# base3-5pin-interface.net
KiCad netlist of a schematic drawn in EAGLE
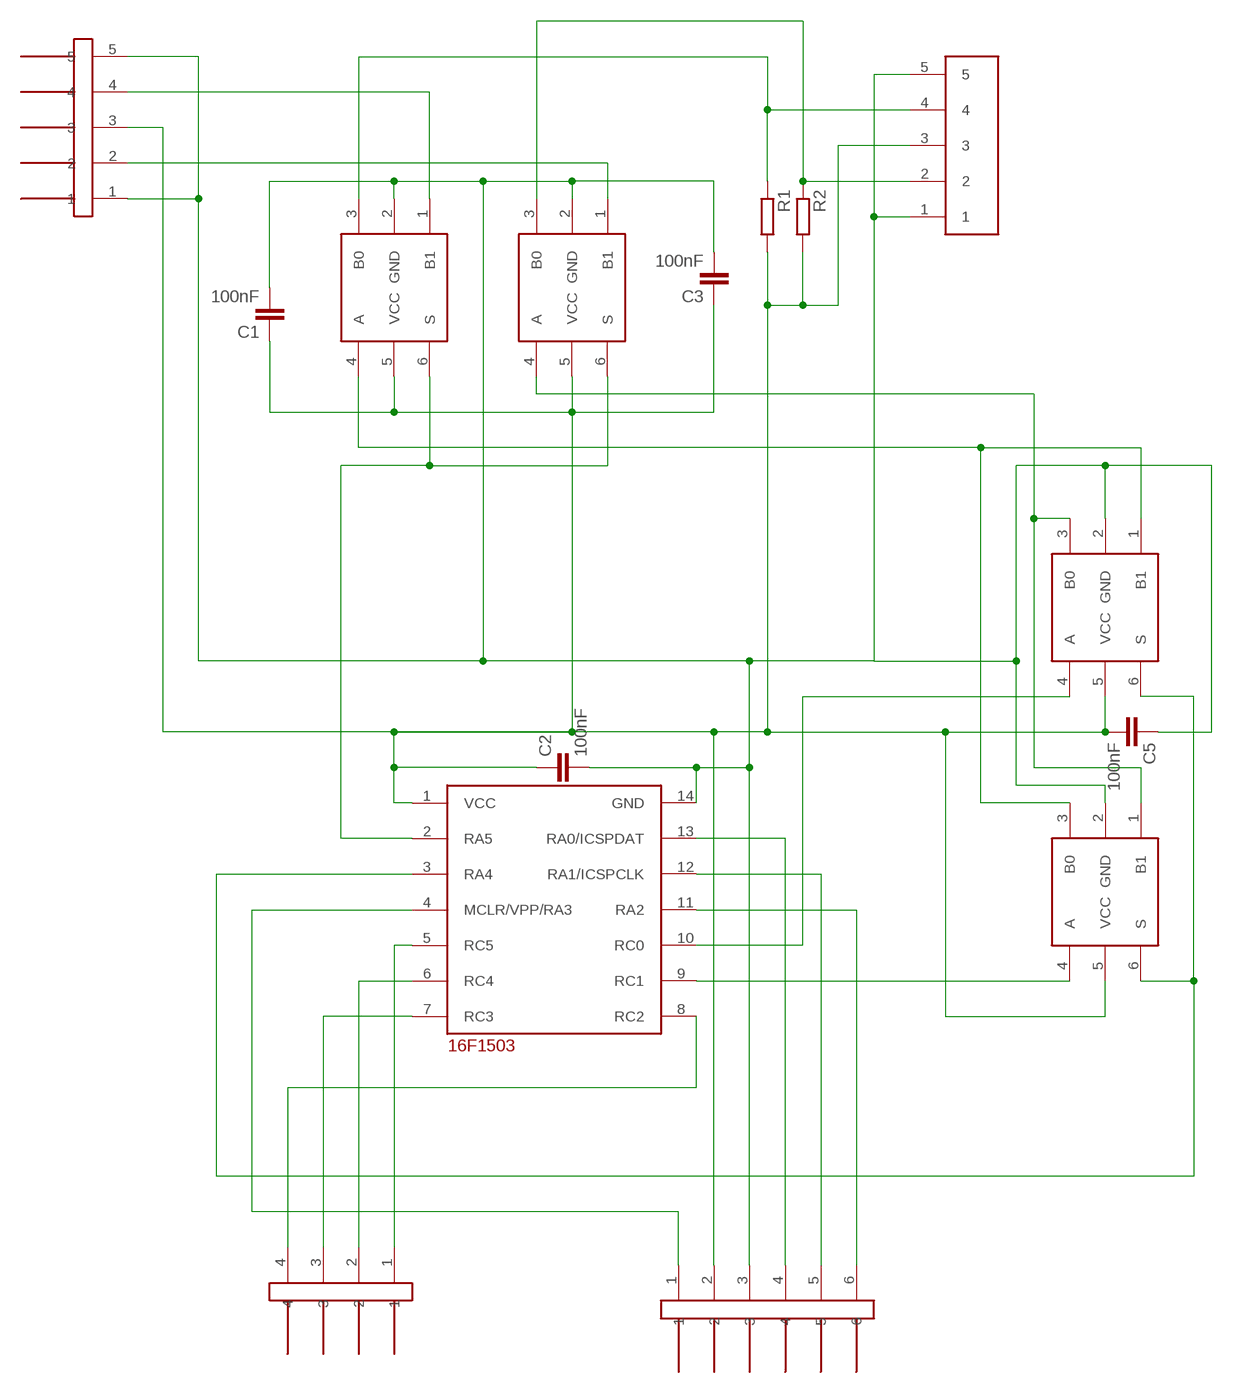
[diagram p0: schematic, sheet 1]

(export (version "E")
  (design (tool "Eeschema 10.0.6"))
  (components
    (comp (ref "C1")
      (value "100nF")
      (footprint "eagle-import:C0805")
      (libsource (lib "eagle-import") (part "C-EUC0805"))
    )
    (comp (ref "C2")
      (value "100nF")
      (footprint "eagle-import:C0805")
      (libsource (lib "eagle-import") (part "C-EUC0805"))
    )
    (comp (ref "C3")
      (value "100nF")
      (footprint "eagle-import:C0805")
      (libsource (lib "eagle-import") (part "C-EUC0805"))
    )
    (comp (ref "C5")
      (value "100nF")
      (footprint "eagle-import:C0805")
      (libsource (lib "eagle-import") (part "C-EUC0805"))
    )
    (comp (ref "IO")
      (value "JUMPER4M")
      (footprint "eagle-import:JUMPER4M")
      (libsource (lib "eagle-import") (part "JUMPER4M"))
    )
    (comp (ref "PROGRAMMER")
      (value "JUMPER6M")
      (footprint "eagle-import:JUMPER6M")
      (libsource (lib "eagle-import") (part "JUMPER6M"))
    )
    (comp (ref "R1")
      (value "R-EU_M0805")
      (footprint "eagle-import:M0805")
      (libsource (lib "eagle-import") (part "R-EU_M0805"))
    )
    (comp (ref "R2")
      (value "R-EU_M0805")
      (footprint "eagle-import:M0805")
      (libsource (lib "eagle-import") (part "R-EU_M0805"))
    )
    (comp (ref "U$1")
      (value "16F103-TSSOP")
      (footprint "eagle-import:TSSOP14")
      (libsource (lib "eagle-import") (part "16F103-TSSOP"))
    )
    (comp (ref "U$2")
      (value "NC7SB3157P6X")
      (footprint "eagle-import:SC70-6L")
      (libsource (lib "eagle-import") (part "NC7SB3157P6X"))
    )
    (comp (ref "U$3")
      (value "NC7SB3157P6X")
      (footprint "eagle-import:SC70-6L")
      (libsource (lib "eagle-import") (part "NC7SB3157P6X"))
    )
    (comp (ref "U$4")
      (value "JUMPER5")
      (footprint "eagle-import:JUMPER5")
      (libsource (lib "eagle-import") (part "JUMPER5"))
    )
    (comp (ref "U$5")
      (value "JUMPER5F")
      (footprint "eagle-import:JUMPER5F")
      (libsource (lib "eagle-import") (part "JUMPER5F"))
    )
    (comp (ref "U$6")
      (value "NC7SB3157P6X")
      (footprint "eagle-import:SC70-6L")
      (libsource (lib "eagle-import") (part "NC7SB3157P6X"))
    )
    (comp (ref "U$7")
      (value "NC7SB3157P6X")
      (footprint "eagle-import:SC70-6L")
      (libsource (lib "eagle-import") (part "NC7SB3157P6X"))
    )
  )
  (nets
    (net (code "1") (name "Net-(U$1-GND)") (class "Default")
      (node (ref "C1") (pin "2") (pinfunction "2_2") (pintype "passive"))
      (node (ref "C2") (pin "2") (pinfunction "2_2") (pintype "passive"))
      (node (ref "C3") (pin "2") (pinfunction "2_2") (pintype "passive"))
      (node (ref "C5") (pin "1") (pinfunction "1_1") (pintype "passive"))
      (node (ref "PROGRAMMER") (pin "3") (pinfunction "3_3") (pintype "bidirectional"))
      (node (ref "U$1") (pin "14") (pinfunction "GND_14") (pintype "power_in"))
      (node (ref "U$2") (pin "2") (pinfunction "GND_2") (pintype "power_in"))
      (node (ref "U$3") (pin "2") (pinfunction "GND_2") (pintype "power_in"))
      (node (ref "U$4") (pin "1") (pinfunction "1_1") (pintype "bidirectional"))
      (node (ref "U$4") (pin "5") (pinfunction "5_5") (pintype "bidirectional"))
      (node (ref "U$5") (pin "1") (pinfunction "1_1") (pintype "bidirectional"))
      (node (ref "U$5") (pin "5") (pinfunction "5_5") (pintype "bidirectional"))
      (node (ref "U$6") (pin "2") (pinfunction "GND_2") (pintype "power_in"))
      (node (ref "U$7") (pin "2") (pinfunction "GND_2") (pintype "power_in"))
    )
    (net (code "2") (name "Net-(U$1-MCLR{slash}VPP{slash}RA3)") (class "Default")
      (node (ref "PROGRAMMER") (pin "1") (pinfunction "1_1") (pintype "bidirectional"))
      (node (ref "U$1") (pin "4") (pinfunction "MCLR/VPP/RA3_4") (pintype "bidirectional"))
    )
    (net (code "3") (name "Net-(U$1-RA0{slash}ICSPDAT)") (class "Default")
      (node (ref "PROGRAMMER") (pin "4") (pinfunction "4_4") (pintype "bidirectional"))
      (node (ref "U$1") (pin "13") (pinfunction "RA0/ICSPDAT_13") (pintype "bidirectional"))
    )
    (net (code "4") (name "Net-(U$1-RA1{slash}ICSPCLK)") (class "Default")
      (node (ref "PROGRAMMER") (pin "5") (pinfunction "5_5") (pintype "bidirectional"))
      (node (ref "U$1") (pin "12") (pinfunction "RA1/ICSPCLK_12") (pintype "bidirectional"))
    )
    (net (code "5") (name "Net-(U$1-RA2)") (class "Default")
      (node (ref "PROGRAMMER") (pin "6") (pinfunction "6_6") (pintype "bidirectional"))
      (node (ref "U$1") (pin "11") (pinfunction "RA2_11") (pintype "bidirectional"))
    )
    (net (code "6") (name "Net-(U$1-RA4)") (class "Default")
      (node (ref "U$1") (pin "3") (pinfunction "RA4_3") (pintype "bidirectional"))
      (node (ref "U$6") (pin "6") (pinfunction "S_6") (pintype "bidirectional"))
      (node (ref "U$7") (pin "6") (pinfunction "S_6") (pintype "bidirectional"))
    )
    (net (code "7") (name "Net-(U$1-RA5)") (class "Default")
      (node (ref "U$1") (pin "2") (pinfunction "RA5_2") (pintype "bidirectional"))
      (node (ref "U$2") (pin "6") (pinfunction "S_6") (pintype "bidirectional"))
      (node (ref "U$3") (pin "6") (pinfunction "S_6") (pintype "bidirectional"))
    )
    (net (code "8") (name "Net-(U$1-RC0)") (class "Default")
      (node (ref "U$1") (pin "10") (pinfunction "RC0_10") (pintype "bidirectional"))
      (node (ref "U$6") (pin "4") (pinfunction "A_4") (pintype "bidirectional"))
    )
    (net (code "9") (name "Net-(U$1-RC1)") (class "Default")
      (node (ref "U$1") (pin "9") (pinfunction "RC1_9") (pintype "bidirectional"))
      (node (ref "U$7") (pin "4") (pinfunction "A_4") (pintype "bidirectional"))
    )
    (net (code "10") (name "Net-(U$1-RC2)") (class "Default")
      (node (ref "IO") (pin "4") (pinfunction "4_4") (pintype "bidirectional"))
      (node (ref "U$1") (pin "8") (pinfunction "RC2_8") (pintype "bidirectional"))
    )
    (net (code "11") (name "Net-(U$1-RC3)") (class "Default")
      (node (ref "IO") (pin "3") (pinfunction "3_3") (pintype "bidirectional"))
      (node (ref "U$1") (pin "7") (pinfunction "RC3_7") (pintype "bidirectional"))
    )
    (net (code "12") (name "Net-(U$1-RC4)") (class "Default")
      (node (ref "IO") (pin "2") (pinfunction "2_2") (pintype "bidirectional"))
      (node (ref "U$1") (pin "6") (pinfunction "RC4_6") (pintype "bidirectional"))
    )
    (net (code "13") (name "Net-(U$1-RC5)") (class "Default")
      (node (ref "IO") (pin "1") (pinfunction "1_1") (pintype "bidirectional"))
      (node (ref "U$1") (pin "5") (pinfunction "RC5_5") (pintype "bidirectional"))
    )
    (net (code "14") (name "Net-(U$1-VCC)") (class "Default")
      (node (ref "C1") (pin "1") (pinfunction "1_1") (pintype "passive"))
      (node (ref "C2") (pin "1") (pinfunction "1_1") (pintype "passive"))
      (node (ref "C3") (pin "1") (pinfunction "1_1") (pintype "passive"))
      (node (ref "C5") (pin "2") (pinfunction "2_2") (pintype "passive"))
      (node (ref "PROGRAMMER") (pin "2") (pinfunction "2_2") (pintype "bidirectional"))
      (node (ref "R1") (pin "2") (pinfunction "2_2") (pintype "passive"))
      (node (ref "R2") (pin "2") (pinfunction "2_2") (pintype "passive"))
      (node (ref "U$1") (pin "1") (pinfunction "VCC_1") (pintype "power_in"))
      (node (ref "U$2") (pin "5") (pinfunction "VCC_5") (pintype "power_in"))
      (node (ref "U$3") (pin "5") (pinfunction "VCC_5") (pintype "power_in"))
      (node (ref "U$4") (pin "3") (pinfunction "3_3") (pintype "bidirectional"))
      (node (ref "U$5") (pin "3") (pinfunction "3_3") (pintype "bidirectional"))
      (node (ref "U$6") (pin "5") (pinfunction "VCC_5") (pintype "power_in"))
      (node (ref "U$7") (pin "5") (pinfunction "VCC_5") (pintype "power_in"))
    )
    (net (code "15") (name "Net-(U$2-A)") (class "Default")
      (node (ref "U$2") (pin "4") (pinfunction "A_4") (pintype "bidirectional"))
      (node (ref "U$6") (pin "1") (pinfunction "B1_1") (pintype "bidirectional"))
      (node (ref "U$7") (pin "3") (pinfunction "B0_3") (pintype "bidirectional"))
    )
    (net (code "16") (name "Net-(U$2-B0)") (class "Default")
      (node (ref "R1") (pin "1") (pinfunction "1_1") (pintype "passive"))
      (node (ref "U$2") (pin "3") (pinfunction "B0_3") (pintype "bidirectional"))
      (node (ref "U$5") (pin "4") (pinfunction "4_4") (pintype "bidirectional"))
    )
    (net (code "17") (name "Net-(U$2-B1)") (class "Default")
      (node (ref "U$2") (pin "1") (pinfunction "B1_1") (pintype "bidirectional"))
      (node (ref "U$4") (pin "4") (pinfunction "4_4") (pintype "bidirectional"))
    )
    (net (code "18") (name "Net-(U$3-A)") (class "Default")
      (node (ref "U$3") (pin "4") (pinfunction "A_4") (pintype "bidirectional"))
      (node (ref "U$6") (pin "3") (pinfunction "B0_3") (pintype "bidirectional"))
      (node (ref "U$7") (pin "1") (pinfunction "B1_1") (pintype "bidirectional"))
    )
    (net (code "19") (name "Net-(U$3-B0)") (class "Default")
      (node (ref "R2") (pin "1") (pinfunction "1_1") (pintype "passive"))
      (node (ref "U$3") (pin "3") (pinfunction "B0_3") (pintype "bidirectional"))
      (node (ref "U$5") (pin "2") (pinfunction "2_2") (pintype "bidirectional"))
    )
    (net (code "20") (name "Net-(U$3-B1)") (class "Default")
      (node (ref "U$3") (pin "1") (pinfunction "B1_1") (pintype "bidirectional"))
      (node (ref "U$4") (pin "2") (pinfunction "2_2") (pintype "bidirectional"))
    )
  )
)
